# HighSide_Analog_protections.net
KiCad netlist of a schematic drawn in Altium Designer
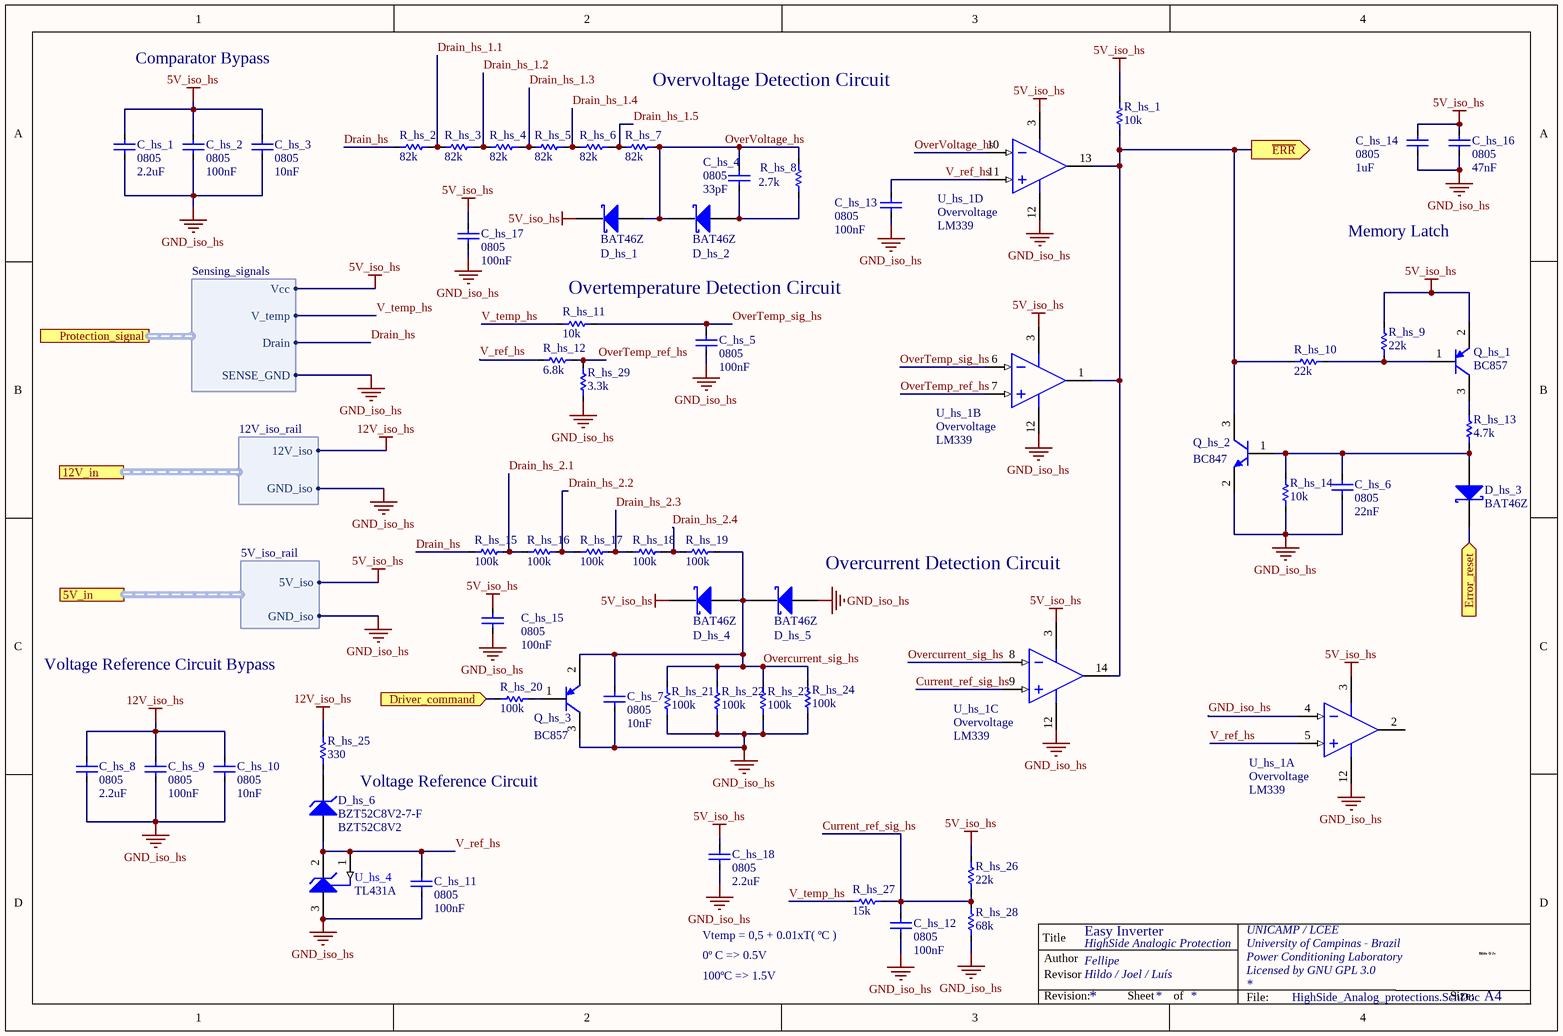
[diagram p0: HighSide_Analog_protections.SchDoc]

(export (version "E")
  (design (tool "Eeschema 10.0.6"))
  (components
    (comp (ref "C_hs_1")
      (value "0805")
      (footprint "Capacitor 0805")
      (description "SMD ceramic capacitor 0805")
      (fields (field (name "ALTIUM_VALUE") "2.2uF"))
      (libsource (lib "EdgeInverter_library") (part "Capacitor 0805"))
    )
    (comp (ref "C_hs_2")
      (value "0805")
      (footprint "Capacitor 0805")
      (description "SMD ceramic capacitor 0805")
      (fields (field (name "ALTIUM_VALUE") "100nF"))
      (libsource (lib "EdgeInverter_library") (part "Capacitor 0805"))
    )
    (comp (ref "C_hs_3")
      (value "0805")
      (footprint "Capacitor 0805")
      (description "SMD ceramic capacitor 0805")
      (fields (field (name "ALTIUM_VALUE") "10nF"))
      (libsource (lib "EdgeInverter_library") (part "Capacitor 0805"))
    )
    (comp (ref "C_hs_4")
      (value "0805")
      (footprint "Capacitor 0805")
      (description "SMD ceramic capacitor 0805")
      (fields (field (name "ALTIUM_VALUE") "33pF"))
      (libsource (lib "EdgeInverter_library") (part "Capacitor 0805"))
    )
    (comp (ref "C_hs_5")
      (value "0805")
      (footprint "Capacitor 0805")
      (description "SMD ceramic capacitor 0805")
      (fields (field (name "ALTIUM_VALUE") "100nF"))
      (libsource (lib "EdgeInverter_library") (part "Capacitor 0805"))
    )
    (comp (ref "C_hs_6")
      (value "0805")
      (footprint "Capacitor 0805")
      (description "SMD ceramic capacitor 0805")
      (fields (field (name "ALTIUM_VALUE") "22nF"))
      (libsource (lib "EdgeInverter_library") (part "Capacitor 0805"))
    )
    (comp (ref "C_hs_7")
      (value "0805")
      (footprint "Capacitor 0805")
      (description "SMD ceramic capacitor 0805")
      (fields (field (name "ALTIUM_VALUE") "10nF"))
      (libsource (lib "EdgeInverter_library") (part "Capacitor 0805"))
    )
    (comp (ref "C_hs_8")
      (value "0805")
      (footprint "Capacitor 0805")
      (description "SMD ceramic capacitor 0805")
      (fields (field (name "ALTIUM_VALUE") "2.2uF"))
      (libsource (lib "EdgeInverter_library") (part "Capacitor 0805"))
    )
    (comp (ref "C_hs_9")
      (value "0805")
      (footprint "Capacitor 0805")
      (description "SMD ceramic capacitor 0805")
      (fields (field (name "ALTIUM_VALUE") "100nF"))
      (libsource (lib "EdgeInverter_library") (part "Capacitor 0805"))
    )
    (comp (ref "C_hs_10")
      (value "0805")
      (footprint "Capacitor 0805")
      (description "SMD ceramic capacitor 0805")
      (fields (field (name "ALTIUM_VALUE") "10nF"))
      (libsource (lib "EdgeInverter_library") (part "Capacitor 0805"))
    )
    (comp (ref "C_hs_11")
      (value "0805")
      (footprint "Capacitor 0805")
      (description "SMD ceramic capacitor 0805")
      (fields (field (name "ALTIUM_VALUE") "100nF"))
      (libsource (lib "EdgeInverter_library") (part "Capacitor 0805"))
    )
    (comp (ref "C_hs_12")
      (value "0805")
      (footprint "Capacitor 0805")
      (description "SMD ceramic capacitor 0805")
      (fields (field (name "ALTIUM_VALUE") "100nF"))
      (libsource (lib "EdgeInverter_library") (part "Capacitor 0805"))
    )
    (comp (ref "C_hs_13")
      (value "0805")
      (footprint "Capacitor 0805")
      (description "SMD ceramic capacitor 0805")
      (fields (field (name "ALTIUM_VALUE") "100nF"))
      (libsource (lib "EdgeInverter_library") (part "Capacitor 0805"))
    )
    (comp (ref "C_hs_14")
      (value "0805")
      (footprint "Capacitor 0805")
      (description "SMD ceramic capacitor 0805")
      (fields (field (name "ALTIUM_VALUE") "1uF"))
      (libsource (lib "EdgeInverter_library") (part "Capacitor 0805"))
    )
    (comp (ref "C_hs_15")
      (value "0805")
      (footprint "Capacitor 0805")
      (description "SMD ceramic capacitor 0805")
      (fields (field (name "ALTIUM_VALUE") "100nF"))
      (libsource (lib "EdgeInverter_library") (part "Capacitor 0805"))
    )
    (comp (ref "C_hs_16")
      (value "0805")
      (footprint "Capacitor 0805")
      (description "SMD ceramic capacitor 0805")
      (fields (field (name "ALTIUM_VALUE") "47nF"))
      (libsource (lib "EdgeInverter_library") (part "Capacitor 0805"))
    )
    (comp (ref "C_hs_17")
      (value "0805")
      (footprint "Capacitor 0805")
      (description "SMD ceramic capacitor 0805")
      (fields (field (name "ALTIUM_VALUE") "100nF"))
      (libsource (lib "EdgeInverter_library") (part "Capacitor 0805"))
    )
    (comp (ref "C_hs_18")
      (value "0805")
      (footprint "Capacitor 0805")
      (description "SMD ceramic capacitor 0805")
      (fields (field (name "ALTIUM_VALUE") "2.2uF"))
      (libsource (lib "EdgeInverter_library") (part "Capacitor 0805"))
    )
    (comp (ref "D_hs_1")
      (value "BAT46Z")
      (footprint "SOD 123")
      (description "DIODE SCHOTTKY 100V 150MA SOD123")
      (libsource (lib "EdgeInverter_library") (part "BAT46Z"))
    )
    (comp (ref "D_hs_2")
      (value "BAT46Z")
      (footprint "SOD 123")
      (description "DIODE SCHOTTKY 100V 150MA SOD123")
      (libsource (lib "EdgeInverter_library") (part "BAT46Z"))
    )
    (comp (ref "D_hs_3")
      (value "BAT46Z")
      (footprint "SOD 123")
      (description "DIODE SCHOTTKY 100V 150MA SOD123")
      (libsource (lib "EdgeInverter_library") (part "BAT46Z"))
    )
    (comp (ref "D_hs_4")
      (value "BAT46Z")
      (footprint "SOD 123")
      (description "DIODE SCHOTTKY 100V 150MA SOD123")
      (libsource (lib "EdgeInverter_library") (part "BAT46Z"))
    )
    (comp (ref "D_hs_5")
      (value "BAT46Z")
      (footprint "SOD 123")
      (description "DIODE SCHOTTKY 100V 150MA SOD123")
      (libsource (lib "EdgeInverter_library") (part "BAT46Z"))
    )
    (comp (ref "D_hs_6")
      (value "BZT52C8V2-7-F")
      (footprint "SOD 123")
      (description "DIODE ZENER 8.2V 500MW SOD123")
      (fields (field (name "ALTIUM_VALUE") "BZT52C8V2"))
      (libsource (lib "EdgeInverter_library") (part "BZT52C8V2-7-F"))
    )
    (comp (ref "Q_hs_1")
      (value "BC857")
      (footprint "SOT 23")
      (description "General Purpose Transistor, PNP Silicon, 3-Pin SOT-23, Pb-Free, Tape and Reel")
      (libsource (lib "EdgeInverter_library") (part "BC857BLT1G"))
    )
    (comp (ref "Q_hs_2")
      (value "BC847")
      (footprint "SOT 23")
      (description "General Purpose Transistor, NPN Silicon, 3-Pin SOT-23, Pb-Free, Tape and Reel")
      (libsource (lib "EdgeInverter_library") (part "BC847BLT1G"))
    )
    (comp (ref "Q_hs_3")
      (value "BC857")
      (footprint "SOT 23")
      (description "General Purpose Transistor, PNP Silicon, 3-Pin SOT-23, Pb-Free, Tape and Reel")
      (libsource (lib "EdgeInverter_library") (part "BC857BLT1G"))
    )
    (comp (ref "R_hs_1")
      (value "10k")
      (footprint "Resistor 0805")
      (description "SMD resistor 0805")
      (fields (field (name "Comment") "Resistor 0805"))
      (libsource (lib "EdgeInverter_library") (part "Resistor 0805"))
    )
    (comp (ref "R_hs_2")
      (value "82k")
      (footprint "Resistor 0805")
      (description "SMD resistor 0805")
      (fields (field (name "Comment") "Resistor 0805"))
      (libsource (lib "EdgeInverter_library") (part "Resistor 0805"))
    )
    (comp (ref "R_hs_3")
      (value "82k")
      (footprint "Resistor 0805")
      (description "SMD resistor 0805")
      (fields (field (name "Comment") "Resistor 0805"))
      (libsource (lib "EdgeInverter_library") (part "Resistor 0805"))
    )
    (comp (ref "R_hs_4")
      (value "82k")
      (footprint "Resistor 0805")
      (description "SMD resistor 0805")
      (fields (field (name "Comment") "Resistor 0805"))
      (libsource (lib "EdgeInverter_library") (part "Resistor 0805"))
    )
    (comp (ref "R_hs_5")
      (value "82k")
      (footprint "Resistor 0805")
      (description "SMD resistor 0805")
      (fields (field (name "Comment") "Resistor 0805"))
      (libsource (lib "EdgeInverter_library") (part "Resistor 0805"))
    )
    (comp (ref "R_hs_6")
      (value "82k")
      (footprint "Resistor 0805")
      (description "SMD resistor 0805")
      (fields (field (name "Comment") "Resistor 0805"))
      (libsource (lib "EdgeInverter_library") (part "Resistor 0805"))
    )
    (comp (ref "R_hs_7")
      (value "82k")
      (footprint "Resistor 0805")
      (description "SMD resistor 0805")
      (fields (field (name "Comment") "Resistor 0805"))
      (libsource (lib "EdgeInverter_library") (part "Resistor 0805"))
    )
    (comp (ref "R_hs_8")
      (value "2.7k")
      (footprint "Resistor 0805")
      (description "SMD resistor 0805")
      (fields (field (name "Comment") "Resistor 0805"))
      (libsource (lib "EdgeInverter_library") (part "Resistor 0805"))
    )
    (comp (ref "R_hs_9")
      (value "22k")
      (footprint "Resistor 0805")
      (description "SMD resistor 0805")
      (fields (field (name "Comment") "Resistor 0805"))
      (libsource (lib "EdgeInverter_library") (part "Resistor 0805"))
    )
    (comp (ref "R_hs_10")
      (value "22k")
      (footprint "Resistor 0805")
      (description "SMD resistor 0805")
      (fields (field (name "Comment") "Resistor 0805"))
      (libsource (lib "EdgeInverter_library") (part "Resistor 0805"))
    )
    (comp (ref "R_hs_11")
      (value "10k")
      (footprint "Resistor 0805")
      (description "SMD resistor 0805")
      (fields (field (name "Comment") "Resistor 0805"))
      (libsource (lib "EdgeInverter_library") (part "Resistor 0805"))
    )
    (comp (ref "R_hs_12")
      (value "6.8k")
      (footprint "Resistor 0805")
      (description "SMD resistor 0805")
      (fields (field (name "Comment") "Resistor 0805"))
      (libsource (lib "EdgeInverter_library") (part "Resistor 0805"))
    )
    (comp (ref "R_hs_13")
      (value "4.7k")
      (footprint "Resistor 0805")
      (description "SMD resistor 0805")
      (fields (field (name "Comment") "Resistor 0805"))
      (libsource (lib "EdgeInverter_library") (part "Resistor 0805"))
    )
    (comp (ref "R_hs_14")
      (value "10k")
      (footprint "Resistor 0805")
      (description "SMD resistor 0805")
      (fields (field (name "Comment") "Resistor 0805"))
      (libsource (lib "EdgeInverter_library") (part "Resistor 0805"))
    )
    (comp (ref "R_hs_15")
      (value "100k")
      (footprint "Resistor 0805")
      (description "SMD resistor 0805")
      (fields (field (name "Comment") "Resistor 0805"))
      (libsource (lib "EdgeInverter_library") (part "Resistor 0805"))
    )
    (comp (ref "R_hs_16")
      (value "100k")
      (footprint "Resistor 0805")
      (description "SMD resistor 0805")
      (fields (field (name "Comment") "Resistor 0805"))
      (libsource (lib "EdgeInverter_library") (part "Resistor 0805"))
    )
    (comp (ref "R_hs_17")
      (value "100k")
      (footprint "Resistor 0805")
      (description "SMD resistor 0805")
      (fields (field (name "Comment") "Resistor 0805"))
      (libsource (lib "EdgeInverter_library") (part "Resistor 0805"))
    )
    (comp (ref "R_hs_18")
      (value "100k")
      (footprint "Resistor 0805")
      (description "SMD resistor 0805")
      (fields (field (name "Comment") "Resistor 0805"))
      (libsource (lib "EdgeInverter_library") (part "Resistor 0805"))
    )
    (comp (ref "R_hs_19")
      (value "100k")
      (footprint "Resistor 0805")
      (description "SMD resistor 0805")
      (fields (field (name "Comment") "Resistor 0805"))
      (libsource (lib "EdgeInverter_library") (part "Resistor 0805"))
    )
    (comp (ref "R_hs_20")
      (value "100k")
      (footprint "Resistor 0805")
      (description "SMD resistor 0805")
      (fields (field (name "Comment") "Resistor 0805"))
      (libsource (lib "EdgeInverter_library") (part "Resistor 0805"))
    )
    (comp (ref "R_hs_21")
      (value "100k")
      (footprint "Resistor 0805")
      (description "SMD resistor 0805")
      (fields (field (name "Comment") "Resistor 0805"))
      (libsource (lib "EdgeInverter_library") (part "Resistor 0805"))
    )
    (comp (ref "R_hs_22")
      (value "100k")
      (footprint "Resistor 0805")
      (description "SMD resistor 0805")
      (fields (field (name "Comment") "Resistor 0805"))
      (libsource (lib "EdgeInverter_library") (part "Resistor 0805"))
    )
    (comp (ref "R_hs_23")
      (value "100k")
      (footprint "Resistor 0805")
      (description "SMD resistor 0805")
      (fields (field (name "Comment") "Resistor 0805"))
      (libsource (lib "EdgeInverter_library") (part "Resistor 0805"))
    )
    (comp (ref "R_hs_24")
      (value "100k")
      (footprint "Resistor 0805")
      (description "SMD resistor 0805")
      (fields (field (name "Comment") "Resistor 0805"))
      (libsource (lib "EdgeInverter_library") (part "Resistor 0805"))
    )
    (comp (ref "R_hs_25")
      (value "330")
      (footprint "Resistor 0805")
      (description "SMD resistor 0805")
      (fields (field (name "Comment") "Resistor 0805"))
      (libsource (lib "EdgeInverter_library") (part "Resistor 0805"))
    )
    (comp (ref "R_hs_26")
      (value "22k")
      (footprint "Resistor 0805")
      (description "SMD resistor 0805")
      (fields (field (name "Comment") "Resistor 0805"))
      (libsource (lib "EdgeInverter_library") (part "Resistor 0805"))
    )
    (comp (ref "R_hs_27")
      (value "15k")
      (footprint "Resistor 0805")
      (description "SMD resistor 0805")
      (fields (field (name "Comment") "Resistor 0805"))
      (libsource (lib "EdgeInverter_library") (part "Resistor 0805"))
    )
    (comp (ref "R_hs_28")
      (value "68k")
      (footprint "Resistor 0805")
      (description "SMD resistor 0805")
      (fields (field (name "Comment") "Resistor 0805"))
      (libsource (lib "EdgeInverter_library") (part "Resistor 0805"))
    )
    (comp (ref "R_hs_29")
      (value "3.3k")
      (footprint "Resistor 0805")
      (description "SMD resistor 0805")
      (fields (field (name "Comment") "Resistor 0805"))
      (libsource (lib "EdgeInverter_library") (part "Resistor 0805"))
    )
    (comp (ref "U_hs_1")
      (value "Overvoltage")
      (footprint "SOIC 14")
      (description "Low Power Low Offset Voltage Quad Comparator, 14-pin Narrow SOIC")
      (fields (field (name "ALTIUM_VALUE") "LM339"))
      (libsource (lib "EdgeInverter_library") (part "LM339"))
    )
    (comp (ref "U_hs_4")
      (value "TL431A")
      (footprint "SOT 23")
      (description "IC VREF SHUNT ADJ SOT23-3")
      (libsource (lib "EdgeInverter_library") (part "TL431A"))
    )
  )
  (nets
    (net (code "4") (name "/Current_ref_sig_hs") (class "Default")
      (node (ref "C_hs_12") (pin "1") (pinfunction "1_1") (pintype "passive"))
      (node (ref "R_hs_26") (pin "1") (pinfunction "1_1") (pintype "passive"))
      (node (ref "R_hs_27") (pin "2") (pinfunction "2_2") (pintype "passive"))
      (node (ref "R_hs_28") (pin "2") (pinfunction "2_2") (pintype "passive"))
      (node (ref "U_hs_1") (pin "9") (pinfunction "IN3+_9") (pintype "input"))
    )
    (net (code "5") (name "/Drain_hs") (class "Default")
      (node (ref "R_hs_15") (pin "1") (pinfunction "1_1") (pintype "passive"))
      (node (ref "R_hs_2") (pin "1") (pinfunction "1_1") (pintype "passive"))
    )
    (net (code "6") (name "/Drain_hs_1.1") (class "Default")
      (node (ref "R_hs_2") (pin "2") (pinfunction "2_2") (pintype "passive"))
      (node (ref "R_hs_3") (pin "1") (pinfunction "1_1") (pintype "passive"))
    )
    (net (code "7") (name "/Drain_hs_1.2") (class "Default")
      (node (ref "R_hs_3") (pin "2") (pinfunction "2_2") (pintype "passive"))
      (node (ref "R_hs_4") (pin "1") (pinfunction "1_1") (pintype "passive"))
    )
    (net (code "8") (name "/Drain_hs_1.3") (class "Default")
      (node (ref "R_hs_4") (pin "2") (pinfunction "2_2") (pintype "passive"))
      (node (ref "R_hs_5") (pin "1") (pinfunction "1_1") (pintype "passive"))
    )
    (net (code "9") (name "/Drain_hs_1.4") (class "Default")
      (node (ref "R_hs_5") (pin "2") (pinfunction "2_2") (pintype "passive"))
      (node (ref "R_hs_6") (pin "1") (pinfunction "1_1") (pintype "passive"))
    )
    (net (code "10") (name "/Drain_hs_1.5") (class "Default")
      (node (ref "R_hs_6") (pin "2") (pinfunction "2_2") (pintype "passive"))
      (node (ref "R_hs_7") (pin "1") (pinfunction "1_1") (pintype "passive"))
    )
    (net (code "11") (name "/Drain_hs_2.1") (class "Default")
      (node (ref "R_hs_15") (pin "2") (pinfunction "2_2") (pintype "passive"))
      (node (ref "R_hs_16") (pin "1") (pinfunction "1_1") (pintype "passive"))
    )
    (net (code "12") (name "/Drain_hs_2.2") (class "Default")
      (node (ref "R_hs_16") (pin "2") (pinfunction "2_2") (pintype "passive"))
      (node (ref "R_hs_17") (pin "1") (pinfunction "1_1") (pintype "passive"))
    )
    (net (code "13") (name "/Drain_hs_2.3") (class "Default")
      (node (ref "R_hs_17") (pin "2") (pinfunction "2_2") (pintype "passive"))
      (node (ref "R_hs_18") (pin "1") (pinfunction "1_1") (pintype "passive"))
    )
    (net (code "14") (name "/Drain_hs_2.4") (class "Default")
      (node (ref "R_hs_18") (pin "2") (pinfunction "2_2") (pintype "passive"))
      (node (ref "R_hs_19") (pin "1") (pinfunction "1_1") (pintype "passive"))
    )
    (net (code "15") (name "/Driver_command") (class "Default")
      (node (ref "R_hs_20") (pin "2") (pinfunction "2_2") (pintype "passive"))
    )
    (net (code "16") (name "/Error_reset") (class "Default")
      (node (ref "D_hs_3") (pin "2") (pinfunction "K_2") (pintype "passive"))
    )
    (net (code "17") (name "/OverTemp_ref_hs") (class "Default")
      (node (ref "R_hs_12") (pin "2") (pinfunction "2_2") (pintype "passive"))
      (node (ref "R_hs_29") (pin "2") (pinfunction "2_2") (pintype "passive"))
      (node (ref "U_hs_1") (pin "7") (pinfunction "IN2+_7") (pintype "input"))
    )
    (net (code "18") (name "/OverTemp_sig_hs") (class "Default")
      (node (ref "C_hs_5") (pin "1") (pinfunction "1_1") (pintype "passive"))
      (node (ref "R_hs_11") (pin "2") (pinfunction "2_2") (pintype "passive"))
      (node (ref "U_hs_1") (pin "6") (pinfunction "IN2-_6") (pintype "input"))
    )
    (net (code "19") (name "/OverVoltage_hs") (class "Default")
      (node (ref "C_hs_4") (pin "1") (pinfunction "1_1") (pintype "passive"))
      (node (ref "D_hs_1") (pin "1") (pinfunction "A_1") (pintype "passive"))
      (node (ref "D_hs_2") (pin "2") (pinfunction "K_2") (pintype "passive"))
      (node (ref "R_hs_7") (pin "2") (pinfunction "2_2") (pintype "passive"))
      (node (ref "R_hs_8") (pin "2") (pinfunction "2_2") (pintype "passive"))
      (node (ref "U_hs_1") (pin "10") (pinfunction "IN4-_10") (pintype "input"))
    )
    (net (code "20") (name "/Overcurrent_sig_hs") (class "Default")
      (node (ref "C_hs_7") (pin "1") (pinfunction "1_1") (pintype "passive"))
      (node (ref "D_hs_4") (pin "1") (pinfunction "A_1") (pintype "passive"))
      (node (ref "D_hs_5") (pin "2") (pinfunction "K_2") (pintype "passive"))
      (node (ref "Q_hs_3") (pin "2") (pinfunction "E_2") (pintype "passive"))
      (node (ref "R_hs_19") (pin "2") (pinfunction "2_2") (pintype "passive"))
      (node (ref "R_hs_21") (pin "2") (pinfunction "2_2") (pintype "passive"))
      (node (ref "R_hs_22") (pin "2") (pinfunction "2_2") (pintype "passive"))
      (node (ref "R_hs_23") (pin "2") (pinfunction "2_2") (pintype "passive"))
      (node (ref "R_hs_24") (pin "2") (pinfunction "2_2") (pintype "passive"))
      (node (ref "U_hs_1") (pin "8") (pinfunction "IN3-_8") (pintype "input"))
    )
    (net (code "21") (name "/V_ref_hs") (class "Default")
      (node (ref "C_hs_11") (pin "1") (pinfunction "1_1") (pintype "passive"))
      (node (ref "C_hs_13") (pin "1") (pinfunction "1_1") (pintype "passive"))
      (node (ref "D_hs_6") (pin "1") (pinfunction "A_1") (pintype "passive"))
      (node (ref "R_hs_12") (pin "1") (pinfunction "1_1") (pintype "passive"))
      (node (ref "U_hs_1") (pin "11") (pinfunction "IN4+_11") (pintype "input"))
      (node (ref "U_hs_1") (pin "5") (pinfunction "IN1+_5") (pintype "input"))
      (node (ref "U_hs_4") (pin "1") (pinfunction "REF_1") (pintype "input"))
      (node (ref "U_hs_4") (pin "2") (pinfunction "CATHODE_2") (pintype "passive"))
    )
    (net (code "22") (name "/V_temp_hs") (class "Default")
      (node (ref "R_hs_11") (pin "1") (pinfunction "1_1") (pintype "passive"))
      (node (ref "R_hs_27") (pin "1") (pinfunction "1_1") (pintype "passive"))
    )
    (net (code "26") (name "/~{ERR}") (class "Default")
      (node (ref "Q_hs_2") (pin "3") (pinfunction "C_3") (pintype "passive"))
      (node (ref "R_hs_1") (pin "1") (pinfunction "1_1") (pintype "passive"))
      (node (ref "R_hs_10") (pin "1") (pinfunction "1_1") (pintype "passive"))
      (node (ref "U_hs_1") (pin "1") (pinfunction "OUT2_1") (pintype "open_collector"))
      (node (ref "U_hs_1") (pin "13") (pinfunction "OUT4_13") (pintype "open_collector"))
      (node (ref "U_hs_1") (pin "14") (pinfunction "OUT3_14") (pintype "open_collector"))
    )
    (net (code "27") (name "5V_iso_hs") (class "Default")
      (node (ref "C_hs_1") (pin "1") (pinfunction "1_1") (pintype "passive"))
      (node (ref "C_hs_14") (pin "1") (pinfunction "1_1") (pintype "passive"))
      (node (ref "C_hs_15") (pin "1") (pinfunction "1_1") (pintype "passive"))
      (node (ref "C_hs_16") (pin "1") (pinfunction "1_1") (pintype "passive"))
      (node (ref "C_hs_17") (pin "1") (pinfunction "1_1") (pintype "passive"))
      (node (ref "C_hs_18") (pin "1") (pinfunction "1_1") (pintype "passive"))
      (node (ref "C_hs_2") (pin "1") (pinfunction "1_1") (pintype "passive"))
      (node (ref "C_hs_3") (pin "1") (pinfunction "1_1") (pintype "passive"))
      (node (ref "D_hs_1") (pin "2") (pinfunction "K_2") (pintype "passive"))
      (node (ref "D_hs_4") (pin "2") (pinfunction "K_2") (pintype "passive"))
      (node (ref "Q_hs_1") (pin "2") (pinfunction "E_2") (pintype "passive"))
      (node (ref "R_hs_1") (pin "2") (pinfunction "2_2") (pintype "passive"))
      (node (ref "R_hs_26") (pin "2") (pinfunction "2_2") (pintype "passive"))
      (node (ref "R_hs_9") (pin "2") (pinfunction "2_2") (pintype "passive"))
      (node (ref "U_hs_1") (pin "3") (pinfunction "V+_3") (pintype "power_in"))
    )
    (net (code "28") (name "12V_iso_hs") (class "Default")
      (node (ref "C_hs_10") (pin "1") (pinfunction "1_1") (pintype "passive"))
      (node (ref "C_hs_8") (pin "1") (pinfunction "1_1") (pintype "passive"))
      (node (ref "C_hs_9") (pin "1") (pinfunction "1_1") (pintype "passive"))
      (node (ref "R_hs_25") (pin "2") (pinfunction "2_2") (pintype "passive"))
    )
    (net (code "29") (name "GND_iso_hs") (class "Default")
      (node (ref "C_hs_1") (pin "2") (pinfunction "2_2") (pintype "passive"))
      (node (ref "C_hs_10") (pin "2") (pinfunction "2_2") (pintype "passive"))
      (node (ref "C_hs_11") (pin "2") (pinfunction "2_2") (pintype "passive"))
      (node (ref "C_hs_12") (pin "2") (pinfunction "2_2") (pintype "passive"))
      (node (ref "C_hs_13") (pin "2") (pinfunction "2_2") (pintype "passive"))
      (node (ref "C_hs_14") (pin "2") (pinfunction "2_2") (pintype "passive"))
      (node (ref "C_hs_15") (pin "2") (pinfunction "2_2") (pintype "passive"))
      (node (ref "C_hs_16") (pin "2") (pinfunction "2_2") (pintype "passive"))
      (node (ref "C_hs_17") (pin "2") (pinfunction "2_2") (pintype "passive"))
      (node (ref "C_hs_18") (pin "2") (pinfunction "2_2") (pintype "passive"))
      (node (ref "C_hs_2") (pin "2") (pinfunction "2_2") (pintype "passive"))
      (node (ref "C_hs_3") (pin "2") (pinfunction "2_2") (pintype "passive"))
      (node (ref "C_hs_5") (pin "2") (pinfunction "2_2") (pintype "passive"))
      (node (ref "C_hs_6") (pin "2") (pinfunction "2_2") (pintype "passive"))
      (node (ref "C_hs_7") (pin "2") (pinfunction "2_2") (pintype "passive"))
      (node (ref "C_hs_8") (pin "2") (pinfunction "2_2") (pintype "passive"))
      (node (ref "C_hs_9") (pin "2") (pinfunction "2_2") (pintype "passive"))
      (node (ref "D_hs_5") (pin "1") (pinfunction "A_1") (pintype "passive"))
      (node (ref "Q_hs_2") (pin "2") (pinfunction "E_2") (pintype "passive"))
      (node (ref "Q_hs_3") (pin "3") (pinfunction "C_3") (pintype "passive"))
      (node (ref "R_hs_14") (pin "1") (pinfunction "1_1") (pintype "passive"))
      (node (ref "R_hs_21") (pin "1") (pinfunction "1_1") (pintype "passive"))
      (node (ref "R_hs_22") (pin "1") (pinfunction "1_1") (pintype "passive"))
      (node (ref "R_hs_23") (pin "1") (pinfunction "1_1") (pintype "passive"))
      (node (ref "R_hs_24") (pin "1") (pinfunction "1_1") (pintype "passive"))
      (node (ref "R_hs_28") (pin "1") (pinfunction "1_1") (pintype "passive"))
      (node (ref "R_hs_29") (pin "1") (pinfunction "1_1") (pintype "passive"))
      (node (ref "U_hs_1") (pin "12") (pinfunction "GND_12") (pintype "power_in"))
      (node (ref "U_hs_1") (pin "4") (pinfunction "IN1-_4") (pintype "input"))
      (node (ref "U_hs_4") (pin "3") (pinfunction "ANODE_3") (pintype "passive"))
    )
    (net (code "30") (name "Net-(D_hs_2-A)") (class "Default")
      (node (ref "C_hs_4") (pin "2") (pinfunction "2_2") (pintype "passive"))
      (node (ref "D_hs_2") (pin "1") (pinfunction "A_1") (pintype "passive"))
      (node (ref "R_hs_8") (pin "1") (pinfunction "1_1") (pintype "passive"))
    )
    (net (code "31") (name "Net-(D_hs_3-A)") (class "Default")
      (node (ref "C_hs_6") (pin "1") (pinfunction "1_1") (pintype "passive"))
      (node (ref "D_hs_3") (pin "1") (pinfunction "A_1") (pintype "passive"))
      (node (ref "Q_hs_2") (pin "1") (pinfunction "B_1") (pintype "passive"))
      (node (ref "R_hs_13") (pin "1") (pinfunction "1_1") (pintype "passive"))
      (node (ref "R_hs_14") (pin "2") (pinfunction "2_2") (pintype "passive"))
    )
    (net (code "32") (name "Net-(D_hs_6-K)") (class "Default")
      (node (ref "D_hs_6") (pin "2") (pinfunction "K_2") (pintype "passive"))
      (node (ref "R_hs_25") (pin "1") (pinfunction "1_1") (pintype "passive"))
    )
    (net (code "33") (name "Net-(Q_hs_1-B)") (class "Default")
      (node (ref "Q_hs_1") (pin "1") (pinfunction "B_1") (pintype "passive"))
      (node (ref "R_hs_10") (pin "2") (pinfunction "2_2") (pintype "passive"))
      (node (ref "R_hs_9") (pin "1") (pinfunction "1_1") (pintype "passive"))
    )
    (net (code "34") (name "Net-(Q_hs_1-C)") (class "Default")
      (node (ref "Q_hs_1") (pin "3") (pinfunction "C_3") (pintype "passive"))
      (node (ref "R_hs_13") (pin "2") (pinfunction "2_2") (pintype "passive"))
    )
    (net (code "35") (name "Net-(Q_hs_3-B)") (class "Default")
      (node (ref "Q_hs_3") (pin "1") (pinfunction "B_1") (pintype "passive"))
      (node (ref "R_hs_20") (pin "1") (pinfunction "1_1") (pintype "passive"))
    )
    (net (code "36") (name "unconnected-(U_hs_1A-OUT1-Pad2)") (class "Default")
      (node (ref "U_hs_1") (pin "2") (pinfunction "OUT1_2") (pintype "open_collector"))
    )
  )
)
